# power.net
KiCad netlist of a schematic drawn in Altium Designer
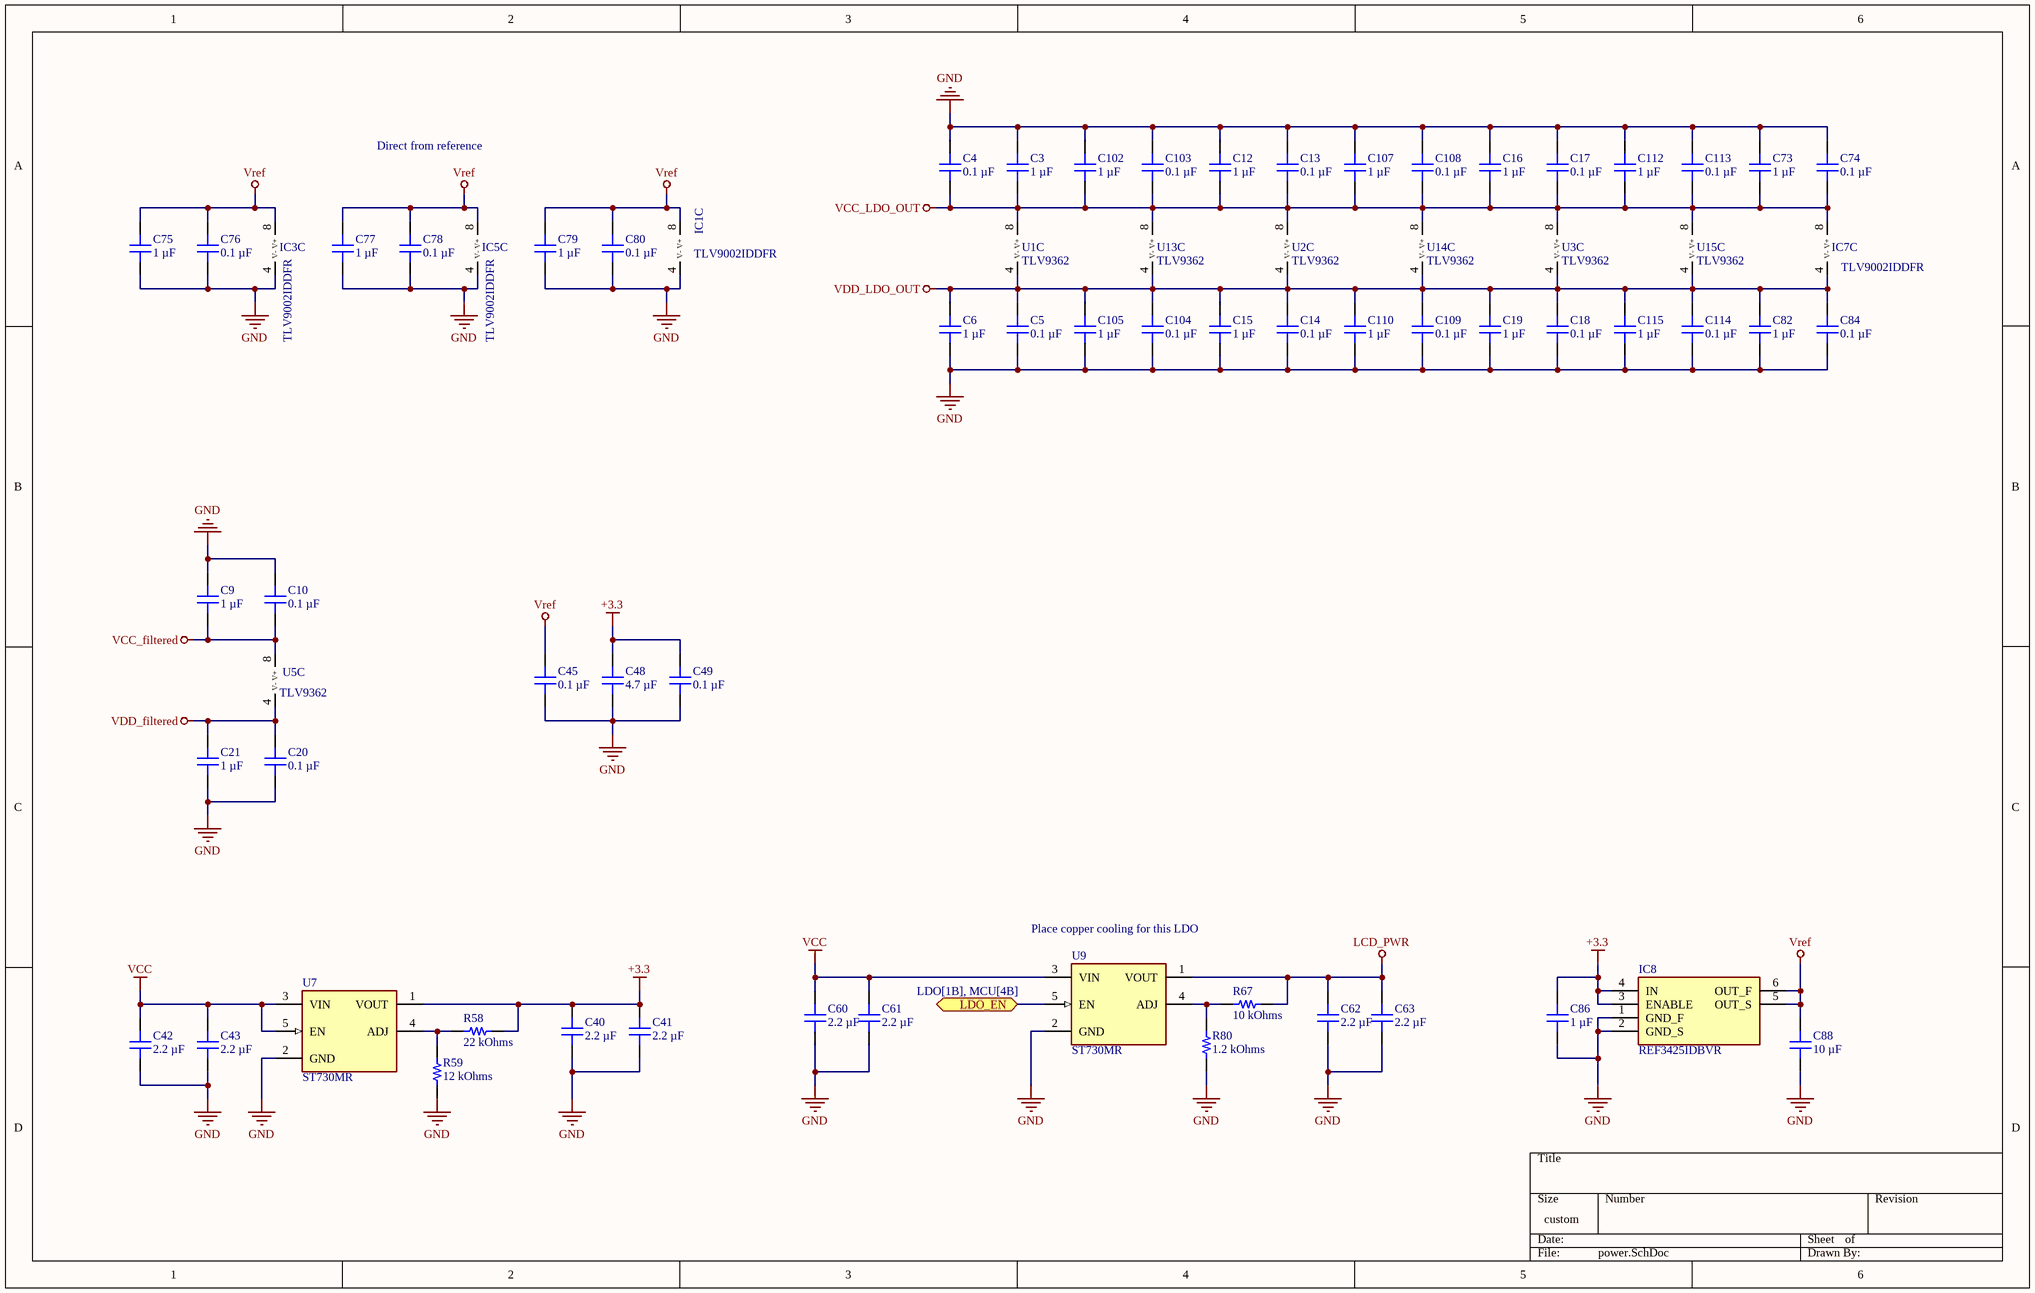
[diagram p0: power.SchDoc]

(export (version "E")
  (design (tool "Eeschema 10.0.6"))
  (components
    (comp (ref "C3")
      (value "1 µF")
      (footprint "CAP 1206_3216 - 0.8MM")
      (description "CAP CER 1UF 50V X7R 1206")
      (fields
        (field (name "PART NUMBER") "885012208093")
        (field (name "CAPACITANCE") "1 µF")
        (field (name "MANUFACTURER") "Würth Elektronik")
      )
      (libsource (lib "Celestial Altium Library - altium_library") (part "Capacitor"))
    )
    (comp (ref "C4")
      (value "0.1 µF")
      (footprint "CAP 1206_3216 - 0.8MM")
      (description "CAP CER 0.1UF 50V X7R 1206")
      (fields
        (field (name "PART NUMBER") "885012208087")
        (field (name "CAPACITANCE") "0.1 µF")
        (field (name "MANUFACTURER") "Würth Elektronik")
      )
      (libsource (lib "Celestial Altium Library - altium_library") (part "Capacitor"))
    )
    (comp (ref "C5")
      (value "0.1 µF")
      (footprint "CAP 1206_3216 - 0.8MM")
      (description "CAP CER 0.1UF 50V X7R 1206")
      (fields
        (field (name "PART NUMBER") "885012208087")
        (field (name "CAPACITANCE") "0.1 µF")
        (field (name "MANUFACTURER") "Würth Elektronik")
      )
      (libsource (lib "Celestial Altium Library - altium_library") (part "Capacitor"))
    )
    (comp (ref "C6")
      (value "1 µF")
      (footprint "CAP 1206_3216 - 0.8MM")
      (description "CAP CER 1UF 50V X7R 1206")
      (fields
        (field (name "PART NUMBER") "885012208093")
        (field (name "CAPACITANCE") "1 µF")
        (field (name "MANUFACTURER") "Würth Elektronik")
      )
      (libsource (lib "Celestial Altium Library - altium_library") (part "Capacitor"))
    )
    (comp (ref "C9")
      (value "1 µF")
      (footprint "CAP 1206_3216 - 0.8MM")
      (description "CAP CER 1UF 50V X7R 1206")
      (fields
        (field (name "PART NUMBER") "885012208093")
        (field (name "CAPACITANCE") "1 µF")
        (field (name "MANUFACTURER") "Würth Elektronik")
      )
      (libsource (lib "Celestial Altium Library - altium_library") (part "Capacitor"))
    )
    (comp (ref "C10")
      (value "0.1 µF")
      (footprint "CAP 1206_3216 - 0.8MM")
      (description "CAP CER 0.1UF 50V X7R 1206")
      (fields
        (field (name "PART NUMBER") "885012208087")
        (field (name "CAPACITANCE") "0.1 µF")
        (field (name "MANUFACTURER") "Würth Elektronik")
      )
      (libsource (lib "Celestial Altium Library - altium_library") (part "Capacitor"))
    )
    (comp (ref "C12")
      (value "1 µF")
      (footprint "CAP 1206_3216 - 0.8MM")
      (description "CAP CER 1UF 50V X7R 1206")
      (fields
        (field (name "PART NUMBER") "885012208093")
        (field (name "CAPACITANCE") "1 µF")
        (field (name "MANUFACTURER") "Würth Elektronik")
      )
      (libsource (lib "Celestial Altium Library - altium_library") (part "Capacitor"))
    )
    (comp (ref "C13")
      (value "0.1 µF")
      (footprint "CAP 1206_3216 - 0.8MM")
      (description "CAP CER 0.1UF 50V X7R 1206")
      (fields
        (field (name "PART NUMBER") "885012208087")
        (field (name "CAPACITANCE") "0.1 µF")
        (field (name "MANUFACTURER") "Würth Elektronik")
      )
      (libsource (lib "Celestial Altium Library - altium_library") (part "Capacitor"))
    )
    (comp (ref "C14")
      (value "0.1 µF")
      (footprint "CAP 1206_3216 - 0.8MM")
      (description "CAP CER 0.1UF 50V X7R 1206")
      (fields
        (field (name "PART NUMBER") "885012208087")
        (field (name "CAPACITANCE") "0.1 µF")
        (field (name "MANUFACTURER") "Würth Elektronik")
      )
      (libsource (lib "Celestial Altium Library - altium_library") (part "Capacitor"))
    )
    (comp (ref "C15")
      (value "1 µF")
      (footprint "CAP 1206_3216 - 0.8MM")
      (description "CAP CER 1UF 50V X7R 1206")
      (fields
        (field (name "PART NUMBER") "885012208093")
        (field (name "CAPACITANCE") "1 µF")
        (field (name "MANUFACTURER") "Würth Elektronik")
      )
      (libsource (lib "Celestial Altium Library - altium_library") (part "Capacitor"))
    )
    (comp (ref "C16")
      (value "1 µF")
      (footprint "CAP 1206_3216 - 0.8MM")
      (description "CAP CER 1UF 50V X7R 1206")
      (fields
        (field (name "PART NUMBER") "885012208093")
        (field (name "CAPACITANCE") "1 µF")
        (field (name "MANUFACTURER") "Würth Elektronik")
      )
      (libsource (lib "Celestial Altium Library - altium_library") (part "Capacitor"))
    )
    (comp (ref "C17")
      (value "0.1 µF")
      (footprint "CAP 1206_3216 - 0.8MM")
      (description "CAP CER 0.1UF 50V X7R 1206")
      (fields
        (field (name "PART NUMBER") "885012208087")
        (field (name "CAPACITANCE") "0.1 µF")
        (field (name "MANUFACTURER") "Würth Elektronik")
      )
      (libsource (lib "Celestial Altium Library - altium_library") (part "Capacitor"))
    )
    (comp (ref "C18")
      (value "0.1 µF")
      (footprint "CAP 1206_3216 - 0.8MM")
      (description "CAP CER 0.1UF 50V X7R 1206")
      (fields
        (field (name "PART NUMBER") "885012208087")
        (field (name "CAPACITANCE") "0.1 µF")
        (field (name "MANUFACTURER") "Würth Elektronik")
      )
      (libsource (lib "Celestial Altium Library - altium_library") (part "Capacitor"))
    )
    (comp (ref "C19")
      (value "1 µF")
      (footprint "CAP 1206_3216 - 0.8MM")
      (description "CAP CER 1UF 50V X7R 1206")
      (fields
        (field (name "PART NUMBER") "885012208093")
        (field (name "CAPACITANCE") "1 µF")
        (field (name "MANUFACTURER") "Würth Elektronik")
      )
      (libsource (lib "Celestial Altium Library - altium_library") (part "Capacitor"))
    )
    (comp (ref "C20")
      (value "0.1 µF")
      (footprint "CAP 1206_3216 - 0.8MM")
      (description "CAP CER 0.1UF 50V X7R 1206")
      (fields
        (field (name "PART NUMBER") "885012208087")
        (field (name "CAPACITANCE") "0.1 µF")
        (field (name "MANUFACTURER") "Würth Elektronik")
      )
      (libsource (lib "Celestial Altium Library - altium_library") (part "Capacitor"))
    )
    (comp (ref "C21")
      (value "1 µF")
      (footprint "CAP 1206_3216 - 0.8MM")
      (description "CAP CER 1UF 50V X7R 1206")
      (fields
        (field (name "PART NUMBER") "885012208093")
        (field (name "CAPACITANCE") "1 µF")
        (field (name "MANUFACTURER") "Würth Elektronik")
      )
      (libsource (lib "Celestial Altium Library - altium_library") (part "Capacitor"))
    )
    (comp (ref "C40")
      (value "2.2 µF")
      (footprint "CAP 1206_3216 - 0.8MM")
      (description "CAP CER 2.2UF 25V X7R 1206")
      (fields
        (field (name "PART NUMBER") "885382208001")
        (field (name "CAPACITANCE") "2.2 µF")
        (field (name "MANUFACTURER") "Würth Elektronik")
      )
      (libsource (lib "Celestial Altium Library - altium_library") (part "Capacitor"))
    )
    (comp (ref "C41")
      (value "2.2 µF")
      (footprint "CAP 1206_3216 - 0.8MM")
      (description "CAP CER 2.2UF 25V X7R 1206")
      (fields
        (field (name "PART NUMBER") "885382208001")
        (field (name "CAPACITANCE") "2.2 µF")
        (field (name "MANUFACTURER") "Würth Elektronik")
      )
      (libsource (lib "Celestial Altium Library - altium_library") (part "Capacitor"))
    )
    (comp (ref "C42")
      (value "2.2 µF")
      (footprint "CAP 1206_3216 - 0.8MM")
      (description "CAP CER 2.2UF 25V X7R 1206")
      (fields
        (field (name "PART NUMBER") "885382208001")
        (field (name "CAPACITANCE") "2.2 µF")
        (field (name "MANUFACTURER") "Würth Elektronik")
      )
      (libsource (lib "Celestial Altium Library - altium_library") (part "Capacitor"))
    )
    (comp (ref "C43")
      (value "2.2 µF")
      (footprint "CAP 1206_3216 - 0.8MM")
      (description "CAP CER 2.2UF 25V X7R 1206")
      (fields
        (field (name "PART NUMBER") "885382208001")
        (field (name "CAPACITANCE") "2.2 µF")
        (field (name "MANUFACTURER") "Würth Elektronik")
      )
      (libsource (lib "Celestial Altium Library - altium_library") (part "Capacitor"))
    )
    (comp (ref "C45")
      (value "0.1 µF")
      (footprint "CAP 1206_3216 - 0.8MM")
      (description "CAP CER 0.1UF 50V X7R 1206")
      (fields
        (field (name "PART NUMBER") "885012208087")
        (field (name "CAPACITANCE") "0.1 µF")
        (field (name "MANUFACTURER") "Würth Elektronik")
      )
      (libsource (lib "Celestial Altium Library - altium_library") (part "Capacitor"))
    )
    (comp (ref "C48")
      (value "4.7 µF")
      (footprint "CAP 1206_3216 - 0.8MM")
      (description "CAP CER 4.7UF 50V X7R 1206")
      (fields
        (field (name "PART NUMBER") "885012208094")
        (field (name "CAPACITANCE") "4.7 µF")
        (field (name "MANUFACTURER") "Würth Elektronik")
      )
      (libsource (lib "Celestial Altium Library - altium_library") (part "Capacitor"))
    )
    (comp (ref "C49")
      (value "0.1 µF")
      (footprint "CAP 1206_3216 - 0.8MM")
      (description "CAP CER 0.1UF 50V X7R 1206")
      (fields
        (field (name "PART NUMBER") "885012208087")
        (field (name "CAPACITANCE") "0.1 µF")
        (field (name "MANUFACTURER") "Würth Elektronik")
      )
      (libsource (lib "Celestial Altium Library - altium_library") (part "Capacitor"))
    )
    (comp (ref "C60")
      (value "2.2 µF")
      (footprint "CAP 1206_3216 - 0.8MM")
      (description "CAP CER 2.2UF 25V X7R 1206")
      (fields
        (field (name "PART NUMBER") "885382208001")
        (field (name "CAPACITANCE") "2.2 µF")
        (field (name "MANUFACTURER") "Würth Elektronik")
      )
      (libsource (lib "Celestial Altium Library - altium_library") (part "Capacitor"))
    )
    (comp (ref "C61")
      (value "2.2 µF")
      (footprint "CAP 1206_3216 - 0.8MM")
      (description "CAP CER 2.2UF 25V X7R 1206")
      (fields
        (field (name "PART NUMBER") "885382208001")
        (field (name "CAPACITANCE") "2.2 µF")
        (field (name "MANUFACTURER") "Würth Elektronik")
      )
      (libsource (lib "Celestial Altium Library - altium_library") (part "Capacitor"))
    )
    (comp (ref "C62")
      (value "2.2 µF")
      (footprint "CAP 1206_3216 - 0.8MM")
      (description "CAP CER 2.2UF 25V X7R 1206")
      (fields
        (field (name "PART NUMBER") "885382208001")
        (field (name "CAPACITANCE") "2.2 µF")
        (field (name "MANUFACTURER") "Würth Elektronik")
      )
      (libsource (lib "Celestial Altium Library - altium_library") (part "Capacitor"))
    )
    (comp (ref "C63")
      (value "2.2 µF")
      (footprint "CAP 1206_3216 - 0.8MM")
      (description "CAP CER 2.2UF 25V X7R 1206")
      (fields
        (field (name "PART NUMBER") "885382208001")
        (field (name "CAPACITANCE") "2.2 µF")
        (field (name "MANUFACTURER") "Würth Elektronik")
      )
      (libsource (lib "Celestial Altium Library - altium_library") (part "Capacitor"))
    )
    (comp (ref "C73")
      (value "1 µF")
      (footprint "CAP 1206_3216 - 0.8MM")
      (description "CAP CER 1UF 50V X7R 1206")
      (fields
        (field (name "PART NUMBER") "885012208093")
        (field (name "CAPACITANCE") "1 µF")
        (field (name "MANUFACTURER") "Würth Elektronik")
      )
      (libsource (lib "Celestial Altium Library - altium_library") (part "Capacitor"))
    )
    (comp (ref "C74")
      (value "0.1 µF")
      (footprint "CAP 1206_3216 - 0.8MM")
      (description "CAP CER 0.1UF 50V X7R 1206")
      (fields
        (field (name "PART NUMBER") "885012208087")
        (field (name "CAPACITANCE") "0.1 µF")
        (field (name "MANUFACTURER") "Würth Elektronik")
      )
      (libsource (lib "Celestial Altium Library - altium_library") (part "Capacitor"))
    )
    (comp (ref "C75")
      (value "1 µF")
      (footprint "CAP 1206_3216 - 0.8MM")
      (description "CAP CER 1UF 50V X7R 1206")
      (fields
        (field (name "PART NUMBER") "885012208093")
        (field (name "CAPACITANCE") "1 µF")
        (field (name "MANUFACTURER") "Würth Elektronik")
      )
      (libsource (lib "Celestial Altium Library - altium_library") (part "Capacitor"))
    )
    (comp (ref "C76")
      (value "0.1 µF")
      (footprint "CAP 1206_3216 - 0.8MM")
      (description "CAP CER 0.1UF 50V X7R 1206")
      (fields
        (field (name "PART NUMBER") "885012208087")
        (field (name "CAPACITANCE") "0.1 µF")
        (field (name "MANUFACTURER") "Würth Elektronik")
      )
      (libsource (lib "Celestial Altium Library - altium_library") (part "Capacitor"))
    )
    (comp (ref "C77")
      (value "1 µF")
      (footprint "CAP 1206_3216 - 0.8MM")
      (description "CAP CER 1UF 50V X7R 1206")
      (fields
        (field (name "PART NUMBER") "885012208093")
        (field (name "CAPACITANCE") "1 µF")
        (field (name "MANUFACTURER") "Würth Elektronik")
      )
      (libsource (lib "Celestial Altium Library - altium_library") (part "Capacitor"))
    )
    (comp (ref "C78")
      (value "0.1 µF")
      (footprint "CAP 1206_3216 - 0.8MM")
      (description "CAP CER 0.1UF 50V X7R 1206")
      (fields
        (field (name "PART NUMBER") "885012208087")
        (field (name "CAPACITANCE") "0.1 µF")
        (field (name "MANUFACTURER") "Würth Elektronik")
      )
      (libsource (lib "Celestial Altium Library - altium_library") (part "Capacitor"))
    )
    (comp (ref "C79")
      (value "1 µF")
      (footprint "CAP 1206_3216 - 0.8MM")
      (description "CAP CER 1UF 50V X7R 1206")
      (fields
        (field (name "PART NUMBER") "885012208093")
        (field (name "CAPACITANCE") "1 µF")
        (field (name "MANUFACTURER") "Würth Elektronik")
      )
      (libsource (lib "Celestial Altium Library - altium_library") (part "Capacitor"))
    )
    (comp (ref "C80")
      (value "0.1 µF")
      (footprint "CAP 1206_3216 - 0.8MM")
      (description "CAP CER 0.1UF 50V X7R 1206")
      (fields
        (field (name "PART NUMBER") "885012208087")
        (field (name "CAPACITANCE") "0.1 µF")
        (field (name "MANUFACTURER") "Würth Elektronik")
      )
      (libsource (lib "Celestial Altium Library - altium_library") (part "Capacitor"))
    )
    (comp (ref "C82")
      (value "1 µF")
      (footprint "CAP 1206_3216 - 0.8MM")
      (description "CAP CER 1UF 50V X7R 1206")
      (fields
        (field (name "PART NUMBER") "885012208093")
        (field (name "CAPACITANCE") "1 µF")
        (field (name "MANUFACTURER") "Würth Elektronik")
      )
      (libsource (lib "Celestial Altium Library - altium_library") (part "Capacitor"))
    )
    (comp (ref "C84")
      (value "0.1 µF")
      (footprint "CAP 1206_3216 - 0.8MM")
      (description "CAP CER 0.1UF 50V X7R 1206")
      (fields
        (field (name "PART NUMBER") "885012208087")
        (field (name "CAPACITANCE") "0.1 µF")
        (field (name "MANUFACTURER") "Würth Elektronik")
      )
      (libsource (lib "Celestial Altium Library - altium_library") (part "Capacitor"))
    )
    (comp (ref "C86")
      (value "1 µF")
      (footprint "CAP 1206_3216 - 0.8MM")
      (description "CAP CER 1UF 50V X7R 1206")
      (fields
        (field (name "PART NUMBER") "885012208093")
        (field (name "CAPACITANCE") "1 µF")
        (field (name "MANUFACTURER") "Würth Elektronik")
      )
      (libsource (lib "Celestial Altium Library - altium_library") (part "Capacitor"))
    )
    (comp (ref "C88")
      (value "10 µF")
      (footprint "CAP 1206_3216 - 0.8MM")
      (description "CAP CER 10UF 25V X7R 1206")
      (fields
        (field (name "PART NUMBER") "885012208069")
        (field (name "CAPACITANCE") "10 µF")
        (field (name "MANUFACTURER") "Würth Elektronik")
      )
      (libsource (lib "Celestial Altium Library - altium_library") (part "Capacitor"))
    )
    (comp (ref "C102")
      (value "1 µF")
      (footprint "CAP 1206_3216 - 0.8MM")
      (description "CAP CER 1UF 50V X7R 1206")
      (fields
        (field (name "PART NUMBER") "885012208093")
        (field (name "CAPACITANCE") "1 µF")
        (field (name "MANUFACTURER") "Würth Elektronik")
      )
      (libsource (lib "Celestial Altium Library - altium_library") (part "Capacitor"))
    )
    (comp (ref "C103")
      (value "0.1 µF")
      (footprint "CAP 1206_3216 - 0.8MM")
      (description "CAP CER 0.1UF 50V X7R 1206")
      (fields
        (field (name "PART NUMBER") "885012208087")
        (field (name "CAPACITANCE") "0.1 µF")
        (field (name "MANUFACTURER") "Würth Elektronik")
      )
      (libsource (lib "Celestial Altium Library - altium_library") (part "Capacitor"))
    )
    (comp (ref "C104")
      (value "0.1 µF")
      (footprint "CAP 1206_3216 - 0.8MM")
      (description "CAP CER 0.1UF 50V X7R 1206")
      (fields
        (field (name "PART NUMBER") "885012208087")
        (field (name "CAPACITANCE") "0.1 µF")
        (field (name "MANUFACTURER") "Würth Elektronik")
      )
      (libsource (lib "Celestial Altium Library - altium_library") (part "Capacitor"))
    )
    (comp (ref "C105")
      (value "1 µF")
      (footprint "CAP 1206_3216 - 0.8MM")
      (description "CAP CER 1UF 50V X7R 1206")
      (fields
        (field (name "PART NUMBER") "885012208093")
        (field (name "CAPACITANCE") "1 µF")
        (field (name "MANUFACTURER") "Würth Elektronik")
      )
      (libsource (lib "Celestial Altium Library - altium_library") (part "Capacitor"))
    )
    (comp (ref "C107")
      (value "1 µF")
      (footprint "CAP 1206_3216 - 0.8MM")
      (description "CAP CER 1UF 50V X7R 1206")
      (fields
        (field (name "PART NUMBER") "885012208093")
        (field (name "CAPACITANCE") "1 µF")
        (field (name "MANUFACTURER") "Würth Elektronik")
      )
      (libsource (lib "Celestial Altium Library - altium_library") (part "Capacitor"))
    )
    (comp (ref "C108")
      (value "0.1 µF")
      (footprint "CAP 1206_3216 - 0.8MM")
      (description "CAP CER 0.1UF 50V X7R 1206")
      (fields
        (field (name "PART NUMBER") "885012208087")
        (field (name "CAPACITANCE") "0.1 µF")
        (field (name "MANUFACTURER") "Würth Elektronik")
      )
      (libsource (lib "Celestial Altium Library - altium_library") (part "Capacitor"))
    )
    (comp (ref "C109")
      (value "0.1 µF")
      (footprint "CAP 1206_3216 - 0.8MM")
      (description "CAP CER 0.1UF 50V X7R 1206")
      (fields
        (field (name "PART NUMBER") "885012208087")
        (field (name "CAPACITANCE") "0.1 µF")
        (field (name "MANUFACTURER") "Würth Elektronik")
      )
      (libsource (lib "Celestial Altium Library - altium_library") (part "Capacitor"))
    )
    (comp (ref "C110")
      (value "1 µF")
      (footprint "CAP 1206_3216 - 0.8MM")
      (description "CAP CER 1UF 50V X7R 1206")
      (fields
        (field (name "PART NUMBER") "885012208093")
        (field (name "CAPACITANCE") "1 µF")
        (field (name "MANUFACTURER") "Würth Elektronik")
      )
      (libsource (lib "Celestial Altium Library - altium_library") (part "Capacitor"))
    )
    (comp (ref "C112")
      (value "1 µF")
      (footprint "CAP 1206_3216 - 0.8MM")
      (description "CAP CER 1UF 50V X7R 1206")
      (fields
        (field (name "PART NUMBER") "885012208093")
        (field (name "CAPACITANCE") "1 µF")
        (field (name "MANUFACTURER") "Würth Elektronik")
      )
      (libsource (lib "Celestial Altium Library - altium_library") (part "Capacitor"))
    )
    (comp (ref "C113")
      (value "0.1 µF")
      (footprint "CAP 1206_3216 - 0.8MM")
      (description "CAP CER 0.1UF 50V X7R 1206")
      (fields
        (field (name "PART NUMBER") "885012208087")
        (field (name "CAPACITANCE") "0.1 µF")
        (field (name "MANUFACTURER") "Würth Elektronik")
      )
      (libsource (lib "Celestial Altium Library - altium_library") (part "Capacitor"))
    )
    (comp (ref "C114")
      (value "0.1 µF")
      (footprint "CAP 1206_3216 - 0.8MM")
      (description "CAP CER 0.1UF 50V X7R 1206")
      (fields
        (field (name "PART NUMBER") "885012208087")
        (field (name "CAPACITANCE") "0.1 µF")
        (field (name "MANUFACTURER") "Würth Elektronik")
      )
      (libsource (lib "Celestial Altium Library - altium_library") (part "Capacitor"))
    )
    (comp (ref "C115")
      (value "1 µF")
      (footprint "CAP 1206_3216 - 0.8MM")
      (description "CAP CER 1UF 50V X7R 1206")
      (fields
        (field (name "PART NUMBER") "885012208093")
        (field (name "CAPACITANCE") "1 µF")
        (field (name "MANUFACTURER") "Würth Elektronik")
      )
      (libsource (lib "Celestial Altium Library - altium_library") (part "Capacitor"))
    )
    (comp (ref "IC1")
      (value "TLV9002IDDFR")
      (footprint "SOT65P280X110-8N")
      (description "Integrated Circuit")
      (fields (field (name "MOUSER PART NUMBER") "595-TLV9002IDDFR"))
      (libsource (lib "za_koncar") (part "TLV9002IDDFR"))
    )
    (comp (ref "IC3")
      (value "TLV9002IDDFR")
      (footprint "SOT65P280X110-8N")
      (description "Integrated Circuit")
      (fields (field (name "MOUSER PART NUMBER") "595-TLV9002IDDFR"))
      (libsource (lib "za_koncar") (part "TLV9002IDDFR"))
    )
    (comp (ref "IC5")
      (value "TLV9002IDDFR")
      (footprint "SOT65P280X110-8N")
      (description "Integrated Circuit")
      (fields (field (name "MOUSER PART NUMBER") "595-TLV9002IDDFR"))
      (libsource (lib "za_koncar") (part "TLV9002IDDFR"))
    )
    (comp (ref "IC7")
      (value "TLV9002IDDFR")
      (footprint "SOT65P280X110-8N")
      (description "Integrated Circuit")
      (fields (field (name "MOUSER PART NUMBER") "595-TLV9002IDDFR"))
      (libsource (lib "za_koncar") (part "TLV9002IDDFR"))
    )
    (comp (ref "IC8")
      (value "REF3425IDBVR")
      (footprint "SOT95P280X145-6N")
      (description "Integrated Circuit")
      (fields (field (name "MOUSER PART NUMBER") "595-REF3425IDBVR"))
      (libsource (lib "za_koncar") (part "REF3425IDBVR"))
    )
    (comp (ref "R58")
      (value "22 kOhms")
      (footprint "YAGEO RES 1206_3216")
      (description "RES SMD 22K OHM 1% 1/4W 1206")
      (fields (field (name "PART NUMBER") "RT1206FRE0722KL") (field (name "MANUFACTURER") "Yageo"))
      (libsource (lib "Celestial Altium Library - altium_library") (part "Resistor"))
    )
    (comp (ref "R59")
      (value "12 kOhms")
      (footprint "YAGEO RES 1206_3216")
      (description "RES SMD 12K OHM 1% 1/4W 1206")
      (fields (field (name "PART NUMBER") "RT1206FRE0712KL") (field (name "MANUFACTURER") "Yageo"))
      (libsource (lib "Celestial Altium Library - altium_library") (part "Resistor"))
    )
    (comp (ref "R67")
      (value "10 kOhms")
      (footprint "YAGEO RES 1206_3216")
      (description "RES SMD 10K OHM 1% 1/4W 1206")
      (fields (field (name "PART NUMBER") "RT1206FRE0710KL") (field (name "MANUFACTURER") "Yageo"))
      (libsource (lib "Celestial Altium Library - altium_library") (part "Resistor"))
    )
    (comp (ref "R80")
      (value "1.2 kOhms")
      (footprint "YAGEO RES 1206_3216")
      (description "RES SMD 1.2K OHM 1% 1/4W 1206")
      (fields (field (name "PART NUMBER") "RT1206FRE071K2L") (field (name "MANUFACTURER") "Yageo"))
      (libsource (lib "Celestial Altium Library - altium_library") (part "Resistor"))
    )
    (comp (ref "U1")
      (value "TLV9362")
      (footprint "za_koncar:SOIC8-127P600X175-8N")
      (description "TLV936x 10-MHz, 40-V, RRO, Operational Amplifie")
      (libsource (lib "za_koncar") (part "TLV9362"))
    )
    (comp (ref "U2")
      (value "TLV9362")
      (footprint "za_koncar:SOIC8-127P600X175-8N")
      (description "TLV936x 10-MHz, 40-V, RRO, Operational Amplifie")
      (libsource (lib "za_koncar") (part "TLV9362"))
    )
    (comp (ref "U3")
      (value "TLV9362")
      (footprint "za_koncar:SOIC8-127P600X175-8N")
      (description "TLV936x 10-MHz, 40-V, RRO, Operational Amplifie")
      (libsource (lib "za_koncar") (part "TLV9362"))
    )
    (comp (ref "U5")
      (value "TLV9362")
      (footprint "za_koncar:SOIC8-127P600X175-8N")
      (description "TLV936x 10-MHz, 40-V, RRO, Operational Amplifie")
      (libsource (lib "za_koncar") (part "TLV9362"))
    )
    (comp (ref "U7")
      (value "ST730MR")
      (footprint "FP-UJ-5-IPC_B")
      (libsource (lib "za_koncar") (part "ST730MR"))
    )
    (comp (ref "U9")
      (value "ST730MR")
      (footprint "FP-UJ-5-IPC_B")
      (libsource (lib "za_koncar") (part "ST730MR"))
    )
    (comp (ref "U13")
      (value "TLV9362")
      (footprint "za_koncar:SOIC8-127P600X175-8N")
      (description "TLV936x 10-MHz, 40-V, RRO, Operational Amplifie")
      (libsource (lib "za_koncar") (part "TLV9362"))
    )
    (comp (ref "U14")
      (value "TLV9362")
      (footprint "za_koncar:SOIC8-127P600X175-8N")
      (description "TLV936x 10-MHz, 40-V, RRO, Operational Amplifie")
      (libsource (lib "za_koncar") (part "TLV9362"))
    )
    (comp (ref "U15")
      (value "TLV9362")
      (footprint "za_koncar:SOIC8-127P600X175-8N")
      (description "TLV936x 10-MHz, 40-V, RRO, Operational Amplifie")
      (libsource (lib "za_koncar") (part "TLV9362"))
    )
  )
  (nets
    (net (code "1") (name "+3.3") (class "Default")
      (node (ref "C40") (pin "2") (pinfunction "2_2") (pintype "passive"))
      (node (ref "C41") (pin "2") (pinfunction "2_2") (pintype "passive"))
      (node (ref "C48") (pin "2") (pinfunction "2_2") (pintype "passive"))
      (node (ref "C49") (pin "2") (pinfunction "2_2") (pintype "passive"))
      (node (ref "C86") (pin "2") (pinfunction "2_2") (pintype "passive"))
      (node (ref "IC8") (pin "3") (pinfunction "ENABLE_3") (pintype "passive"))
      (node (ref "IC8") (pin "4") (pinfunction "IN_4") (pintype "passive"))
      (node (ref "R58") (pin "2") (pinfunction "2_2") (pintype "passive"))
      (node (ref "U7") (pin "1") (pinfunction "VOUT_1") (pintype "power_in"))
    )
    (net (code "2") (name "/LDO_EN") (class "Default")
      (node (ref "U9") (pin "5") (pinfunction "EN_5") (pintype "input"))
    )
    (net (code "3") (name "GND") (class "Default")
      (node (ref "C10") (pin "2") (pinfunction "2_2") (pintype "passive"))
      (node (ref "C102") (pin "2") (pinfunction "2_2") (pintype "passive"))
      (node (ref "C103") (pin "2") (pinfunction "2_2") (pintype "passive"))
      (node (ref "C104") (pin "2") (pinfunction "2_2") (pintype "passive"))
      (node (ref "C105") (pin "2") (pinfunction "2_2") (pintype "passive"))
      (node (ref "C107") (pin "2") (pinfunction "2_2") (pintype "passive"))
      (node (ref "C108") (pin "2") (pinfunction "2_2") (pintype "passive"))
      (node (ref "C109") (pin "2") (pinfunction "2_2") (pintype "passive"))
      (node (ref "C110") (pin "2") (pinfunction "2_2") (pintype "passive"))
      (node (ref "C112") (pin "2") (pinfunction "2_2") (pintype "passive"))
      (node (ref "C113") (pin "2") (pinfunction "2_2") (pintype "passive"))
      (node (ref "C114") (pin "2") (pinfunction "2_2") (pintype "passive"))
      (node (ref "C115") (pin "2") (pinfunction "2_2") (pintype "passive"))
      (node (ref "C12") (pin "2") (pinfunction "2_2") (pintype "passive"))
      (node (ref "C13") (pin "2") (pinfunction "2_2") (pintype "passive"))
      (node (ref "C14") (pin "2") (pinfunction "2_2") (pintype "passive"))
      (node (ref "C15") (pin "2") (pinfunction "2_2") (pintype "passive"))
      (node (ref "C16") (pin "2") (pinfunction "2_2") (pintype "passive"))
      (node (ref "C17") (pin "2") (pinfunction "2_2") (pintype "passive"))
      (node (ref "C18") (pin "2") (pinfunction "2_2") (pintype "passive"))
      (node (ref "C19") (pin "2") (pinfunction "2_2") (pintype "passive"))
      (node (ref "C20") (pin "1") (pinfunction "1_1") (pintype "passive"))
      (node (ref "C21") (pin "1") (pinfunction "1_1") (pintype "passive"))
      (node (ref "C3") (pin "1") (pinfunction "1_1") (pintype "passive"))
      (node (ref "C4") (pin "1") (pinfunction "1_1") (pintype "passive"))
      (node (ref "C40") (pin "1") (pinfunction "1_1") (pintype "passive"))
      (node (ref "C41") (pin "1") (pinfunction "1_1") (pintype "passive"))
      (node (ref "C42") (pin "1") (pinfunction "1_1") (pintype "passive"))
      (node (ref "C43") (pin "1") (pinfunction "1_1") (pintype "passive"))
      (node (ref "C45") (pin "1") (pinfunction "1_1") (pintype "passive"))
      (node (ref "C48") (pin "1") (pinfunction "1_1") (pintype "passive"))
      (node (ref "C49") (pin "1") (pinfunction "1_1") (pintype "passive"))
      (node (ref "C5") (pin "2") (pinfunction "2_2") (pintype "passive"))
      (node (ref "C6") (pin "2") (pinfunction "2_2") (pintype "passive"))
      (node (ref "C60") (pin "1") (pinfunction "1_1") (pintype "passive"))
      (node (ref "C61") (pin "1") (pinfunction "1_1") (pintype "passive"))
      (node (ref "C62") (pin "1") (pinfunction "1_1") (pintype "passive"))
      (node (ref "C63") (pin "1") (pinfunction "1_1") (pintype "passive"))
      (node (ref "C73") (pin "2") (pinfunction "2_2") (pintype "passive"))
      (node (ref "C74") (pin "2") (pinfunction "2_2") (pintype "passive"))
      (node (ref "C75") (pin "1") (pinfunction "1_1") (pintype "passive"))
      (node (ref "C76") (pin "1") (pinfunction "1_1") (pintype "passive"))
      (node (ref "C77") (pin "1") (pinfunction "1_1") (pintype "passive"))
      (node (ref "C78") (pin "1") (pinfunction "1_1") (pintype "passive"))
      (node (ref "C79") (pin "1") (pinfunction "1_1") (pintype "passive"))
      (node (ref "C80") (pin "1") (pinfunction "1_1") (pintype "passive"))
      (node (ref "C82") (pin "2") (pinfunction "2_2") (pintype "passive"))
      (node (ref "C84") (pin "2") (pinfunction "2_2") (pintype "passive"))
      (node (ref "C86") (pin "1") (pinfunction "1_1") (pintype "passive"))
      (node (ref "C88") (pin "1") (pinfunction "1_1") (pintype "passive"))
      (node (ref "C9") (pin "2") (pinfunction "2_2") (pintype "passive"))
      (node (ref "IC1") (pin "4") (pinfunction "V-_4") (pintype "power_in"))
      (node (ref "IC3") (pin "4") (pinfunction "V-_4") (pintype "power_in"))
      (node (ref "IC5") (pin "4") (pinfunction "V-_4") (pintype "power_in"))
      (node (ref "IC8") (pin "1") (pinfunction "GND_F_1") (pintype "passive"))
      (node (ref "IC8") (pin "2") (pinfunction "GND_S_2") (pintype "passive"))
      (node (ref "R59") (pin "2") (pinfunction "2_2") (pintype "passive"))
      (node (ref "R80") (pin "2") (pinfunction "2_2") (pintype "passive"))
      (node (ref "U7") (pin "2") (pinfunction "GND_2") (pintype "power_in"))
      (node (ref "U9") (pin "2") (pinfunction "GND_2") (pintype "power_in"))
    )
    (net (code "4") (name "LCD_PWR") (class "Default")
      (node (ref "C62") (pin "2") (pinfunction "2_2") (pintype "passive"))
      (node (ref "C63") (pin "2") (pinfunction "2_2") (pintype "passive"))
      (node (ref "R67") (pin "2") (pinfunction "2_2") (pintype "passive"))
      (node (ref "U9") (pin "1") (pinfunction "VOUT_1") (pintype "power_in"))
    )
    (net (code "5") (name "Net-(U7-ADJ)") (class "Default")
      (node (ref "R58") (pin "1") (pinfunction "1_1") (pintype "passive"))
      (node (ref "R59") (pin "1") (pinfunction "1_1") (pintype "passive"))
      (node (ref "U7") (pin "4") (pinfunction "ADJ_4") (pintype "passive"))
    )
    (net (code "6") (name "Net-(U9-ADJ)") (class "Default")
      (node (ref "R67") (pin "1") (pinfunction "1_1") (pintype "passive"))
      (node (ref "R80") (pin "1") (pinfunction "1_1") (pintype "passive"))
      (node (ref "U9") (pin "4") (pinfunction "ADJ_4") (pintype "passive"))
    )
    (net (code "7") (name "VCC") (class "Default")
      (node (ref "C42") (pin "2") (pinfunction "2_2") (pintype "passive"))
      (node (ref "C43") (pin "2") (pinfunction "2_2") (pintype "passive"))
      (node (ref "C60") (pin "2") (pinfunction "2_2") (pintype "passive"))
      (node (ref "C61") (pin "2") (pinfunction "2_2") (pintype "passive"))
      (node (ref "U7") (pin "3") (pinfunction "VIN_3") (pintype "power_in"))
      (node (ref "U7") (pin "5") (pinfunction "EN_5") (pintype "input"))
      (node (ref "U9") (pin "3") (pinfunction "VIN_3") (pintype "power_in"))
    )
    (net (code "8") (name "VCC_LDO_OUT") (class "Default")
      (node (ref "C102") (pin "1") (pinfunction "1_1") (pintype "passive"))
      (node (ref "C103") (pin "1") (pinfunction "1_1") (pintype "passive"))
      (node (ref "C107") (pin "1") (pinfunction "1_1") (pintype "passive"))
      (node (ref "C108") (pin "1") (pinfunction "1_1") (pintype "passive"))
      (node (ref "C112") (pin "1") (pinfunction "1_1") (pintype "passive"))
      (node (ref "C113") (pin "1") (pinfunction "1_1") (pintype "passive"))
      (node (ref "C12") (pin "1") (pinfunction "1_1") (pintype "passive"))
      (node (ref "C13") (pin "1") (pinfunction "1_1") (pintype "passive"))
      (node (ref "C16") (pin "1") (pinfunction "1_1") (pintype "passive"))
      (node (ref "C17") (pin "1") (pinfunction "1_1") (pintype "passive"))
      (node (ref "C3") (pin "2") (pinfunction "2_2") (pintype "passive"))
      (node (ref "C4") (pin "2") (pinfunction "2_2") (pintype "passive"))
      (node (ref "C73") (pin "1") (pinfunction "1_1") (pintype "passive"))
      (node (ref "C74") (pin "1") (pinfunction "1_1") (pintype "passive"))
      (node (ref "IC7") (pin "8") (pinfunction "V+_8") (pintype "power_in"))
      (node (ref "U1") (pin "8") (pinfunction "V+_8") (pintype "power_in"))
      (node (ref "U13") (pin "8") (pinfunction "V+_8") (pintype "power_in"))
      (node (ref "U14") (pin "8") (pinfunction "V+_8") (pintype "power_in"))
      (node (ref "U15") (pin "8") (pinfunction "V+_8") (pintype "power_in"))
      (node (ref "U2") (pin "8") (pinfunction "V+_8") (pintype "power_in"))
      (node (ref "U3") (pin "8") (pinfunction "V+_8") (pintype "power_in"))
    )
    (net (code "9") (name "VCC_filtered") (class "Default")
      (node (ref "C10") (pin "1") (pinfunction "1_1") (pintype "passive"))
      (node (ref "C9") (pin "1") (pinfunction "1_1") (pintype "passive"))
      (node (ref "U5") (pin "8") (pinfunction "V+_8") (pintype "power_in"))
    )
    (net (code "10") (name "VDD_LDO_OUT") (class "Default")
      (node (ref "C104") (pin "1") (pinfunction "1_1") (pintype "passive"))
      (node (ref "C105") (pin "1") (pinfunction "1_1") (pintype "passive"))
      (node (ref "C109") (pin "1") (pinfunction "1_1") (pintype "passive"))
      (node (ref "C110") (pin "1") (pinfunction "1_1") (pintype "passive"))
      (node (ref "C114") (pin "1") (pinfunction "1_1") (pintype "passive"))
      (node (ref "C115") (pin "1") (pinfunction "1_1") (pintype "passive"))
      (node (ref "C14") (pin "1") (pinfunction "1_1") (pintype "passive"))
      (node (ref "C15") (pin "1") (pinfunction "1_1") (pintype "passive"))
      (node (ref "C18") (pin "1") (pinfunction "1_1") (pintype "passive"))
      (node (ref "C19") (pin "1") (pinfunction "1_1") (pintype "passive"))
      (node (ref "C5") (pin "1") (pinfunction "1_1") (pintype "passive"))
      (node (ref "C6") (pin "1") (pinfunction "1_1") (pintype "passive"))
      (node (ref "C82") (pin "1") (pinfunction "1_1") (pintype "passive"))
      (node (ref "C84") (pin "1") (pinfunction "1_1") (pintype "passive"))
      (node (ref "IC7") (pin "4") (pinfunction "V-_4") (pintype "power_in"))
      (node (ref "U1") (pin "4") (pinfunction "V-_4") (pintype "power_in"))
      (node (ref "U13") (pin "4") (pinfunction "V-_4") (pintype "power_in"))
      (node (ref "U14") (pin "4") (pinfunction "V-_4") (pintype "power_in"))
      (node (ref "U15") (pin "4") (pinfunction "V-_4") (pintype "power_in"))
      (node (ref "U2") (pin "4") (pinfunction "V-_4") (pintype "power_in"))
      (node (ref "U3") (pin "4") (pinfunction "V-_4") (pintype "power_in"))
    )
    (net (code "11") (name "VDD_filtered") (class "Default")
      (node (ref "C20") (pin "2") (pinfunction "2_2") (pintype "passive"))
      (node (ref "C21") (pin "2") (pinfunction "2_2") (pintype "passive"))
      (node (ref "U5") (pin "4") (pinfunction "V-_4") (pintype "power_in"))
    )
    (net (code "12") (name "Vref") (class "Default")
      (node (ref "C45") (pin "2") (pinfunction "2_2") (pintype "passive"))
      (node (ref "C75") (pin "2") (pinfunction "2_2") (pintype "passive"))
      (node (ref "C76") (pin "2") (pinfunction "2_2") (pintype "passive"))
      (node (ref "C77") (pin "2") (pinfunction "2_2") (pintype "passive"))
      (node (ref "C78") (pin "2") (pinfunction "2_2") (pintype "passive"))
      (node (ref "C79") (pin "2") (pinfunction "2_2") (pintype "passive"))
      (node (ref "C80") (pin "2") (pinfunction "2_2") (pintype "passive"))
      (node (ref "C88") (pin "2") (pinfunction "2_2") (pintype "passive"))
      (node (ref "IC1") (pin "8") (pinfunction "V+_8") (pintype "power_in"))
      (node (ref "IC3") (pin "8") (pinfunction "V+_8") (pintype "power_in"))
      (node (ref "IC5") (pin "8") (pinfunction "V+_8") (pintype "power_in"))
      (node (ref "IC8") (pin "5") (pinfunction "OUT_S_5") (pintype "passive"))
      (node (ref "IC8") (pin "6") (pinfunction "OUT_F_6") (pintype "passive"))
    )
  )
)
